# mechanical.net
KiCad netlist of a schematic drawn in Altium Designer
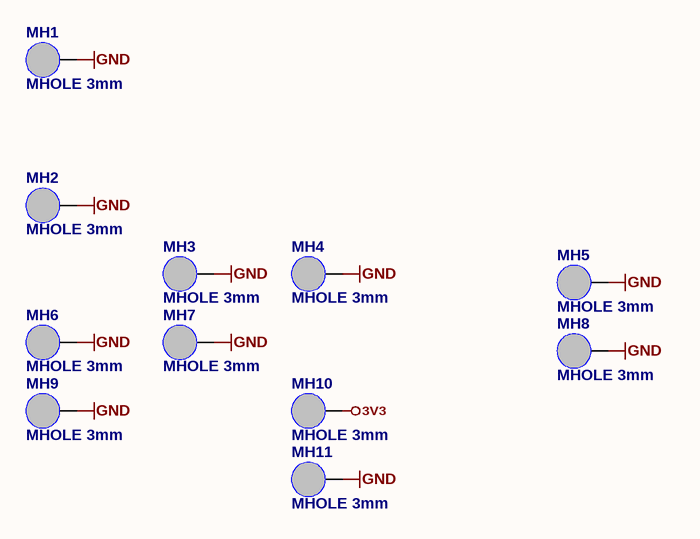
[diagram p0: mechanical.SchDoc]

(export (version "E")
  (design (tool "Eeschema 10.0.6"))
  (components
    (comp (ref "MH1")
      (value "MHOLE 3mm")
      (footprint "3mm screw drill I")
      (description "3mm Mounting Hole")
      (libsource (lib "mechanical_other") (part "MHOLE_3MM"))
    )
    (comp (ref "MH2")
      (value "MHOLE 3mm")
      (footprint "3mm screw drill I")
      (description "3mm Mounting Hole")
      (libsource (lib "mechanical_other") (part "MHOLE_3MM"))
    )
    (comp (ref "MH3")
      (value "MHOLE 3mm")
      (footprint "3mm screw drill I")
      (description "3mm Mounting Hole")
      (libsource (lib "mechanical_other") (part "MHOLE_3MM"))
    )
    (comp (ref "MH4")
      (value "MHOLE 3mm")
      (footprint "3mm screw drill I")
      (description "3mm Mounting Hole")
      (libsource (lib "mechanical_other") (part "MHOLE_3MM"))
    )
    (comp (ref "MH5")
      (value "MHOLE 3mm")
      (footprint "3mm screw drill I")
      (description "3mm Mounting Hole")
      (libsource (lib "mechanical_other") (part "MHOLE_3MM"))
    )
    (comp (ref "MH6")
      (value "MHOLE 3mm")
      (footprint "3mm screw drill I")
      (description "3mm Mounting Hole")
      (libsource (lib "mechanical_other") (part "MHOLE_3MM"))
    )
    (comp (ref "MH7")
      (value "MHOLE 3mm")
      (footprint "3mm screw drill I")
      (description "3mm Mounting Hole")
      (libsource (lib "mechanical_other") (part "MHOLE_3MM"))
    )
    (comp (ref "MH8")
      (value "MHOLE 3mm")
      (footprint "3mm screw drill I")
      (description "3mm Mounting Hole")
      (libsource (lib "mechanical_other") (part "MHOLE_3MM"))
    )
    (comp (ref "MH9")
      (value "MHOLE 3mm")
      (footprint "3mm screw drill I")
      (description "3mm Mounting Hole")
      (libsource (lib "mechanical_other") (part "MHOLE_3MM"))
    )
    (comp (ref "MH10")
      (value "MHOLE 3mm")
      (footprint "3mm screw drill I")
      (description "3mm Mounting Hole")
      (libsource (lib "mechanical_other") (part "MHOLE_3MM"))
    )
    (comp (ref "MH11")
      (value "MHOLE 3mm")
      (footprint "3mm screw drill I")
      (description "3mm Mounting Hole")
      (libsource (lib "mechanical_other") (part "MHOLE_3MM"))
    )
  )
  (nets
    (net (code "1") (name "3V3") (class "Default")
      (node (ref "MH10") (pin "1") (pinfunction "GND_1") (pintype "passive"))
    )
    (net (code "2") (name "GND") (class "Default")
      (node (ref "MH1") (pin "1") (pinfunction "GND_1") (pintype "passive"))
      (node (ref "MH11") (pin "1") (pinfunction "GND_1") (pintype "passive"))
      (node (ref "MH2") (pin "1") (pinfunction "GND_1") (pintype "passive"))
      (node (ref "MH3") (pin "1") (pinfunction "GND_1") (pintype "passive"))
      (node (ref "MH4") (pin "1") (pinfunction "GND_1") (pintype "passive"))
      (node (ref "MH5") (pin "1") (pinfunction "GND_1") (pintype "passive"))
      (node (ref "MH6") (pin "1") (pinfunction "GND_1") (pintype "passive"))
      (node (ref "MH7") (pin "1") (pinfunction "GND_1") (pintype "passive"))
      (node (ref "MH8") (pin "1") (pinfunction "GND_1") (pintype "passive"))
      (node (ref "MH9") (pin "1") (pinfunction "GND_1") (pintype "passive"))
    )
  )
)
